# 2GHz_TDD_Driver.net
KiCad netlist of a schematic drawn in Altium Designer
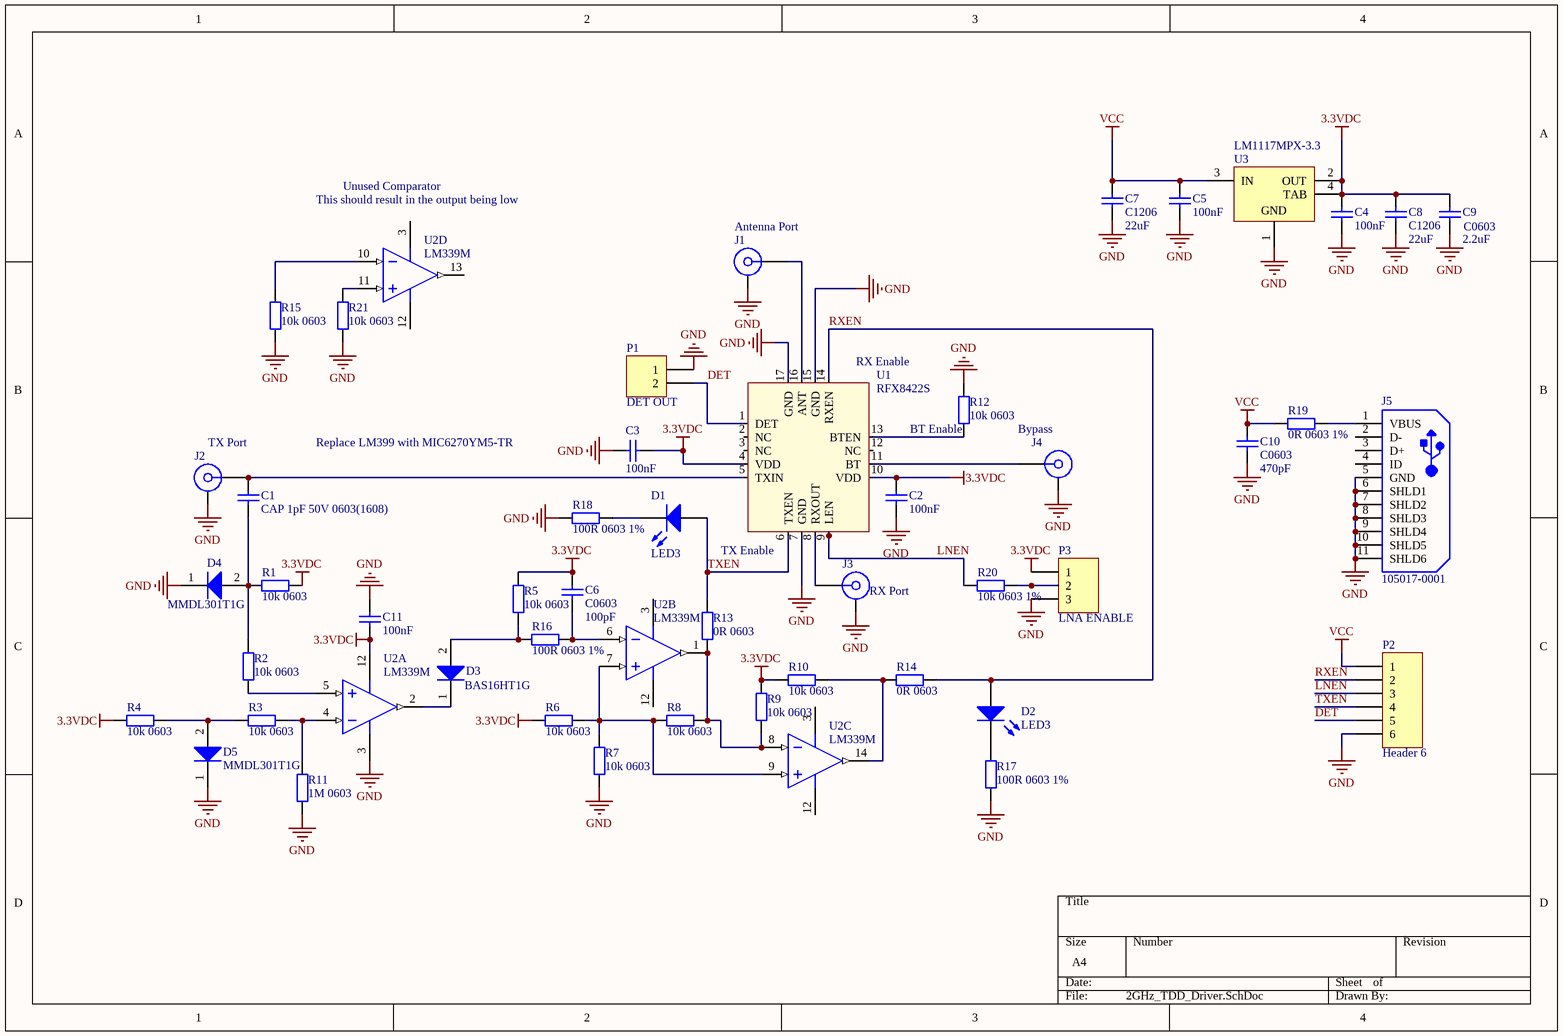
[diagram p0: 2GHz_TDD_Driver.SchDoc]

(export (version "E")
  (design (tool "Eeschema 10.0.6"))
  (components
    (comp (ref "C1")
      (value "CAP 1pF 50V 0603(1608)")
      (footprint "CAPC0603(1608)100_M")
      (description "CAP 1pF 50V ±0.25pF 0603 (1608 Metric) Thickness 1mm SMD")
      (fields (field (name "TOLERANCE") "Â±0.25pF"))
      (libsource (lib "Altium Content Vault") (part "CAP"))
    )
    (comp (ref "C2")
      (value "100nF")
      (footprint "CAPC0603(1608)100_N")
      (description "CAP 100nF 25V ±20% 0603 (1608 Metric) Thickness 1mm SMD")
      (fields (field (name "TOLERANCE") "Â±20%"))
      (libsource (lib "Altium Content Vault") (part "CMP-1035-02589-1"))
    )
    (comp (ref "C3")
      (value "100nF")
      (footprint "CAPC0603(1608)100_N")
      (description "CAP 100nF 25V ±20% 0603 (1608 Metric) Thickness 1mm SMD")
      (fields (field (name "TOLERANCE") "Â±20%"))
      (libsource (lib "Altium Content Vault") (part "CMP-1035-02589-1"))
    )
    (comp (ref "C4")
      (value "100nF")
      (footprint "CAPC0603(1608)100_N")
      (description "CAP 100nF 25V ±20% 0603 (1608 Metric) Thickness 1mm SMD")
      (fields (field (name "TOLERANCE") "Â±20%"))
      (libsource (lib "Altium Content Vault") (part "CMP-1035-02589-1"))
    )
    (comp (ref "C5")
      (value "100nF")
      (footprint "CAPC0603(1608)100_N")
      (description "CAP 100nF 25V ±20% 0603 (1608 Metric) Thickness 1mm SMD")
      (fields (field (name "TOLERANCE") "Â±20%"))
      (libsource (lib "Altium Content Vault") (part "CMP-1035-02589-1"))
    )
    (comp (ref "C6")
      (value "C0603")
      (footprint "0603")
      (description "Ceramic Chip Capacitor - Standard")
      (fields (field (name "ALTIUM_VALUE") "100pF") (field (name "PUBLISHER") "Altium Limited"))
      (libsource (lib "KEMET Chip Capacitor") (part "C0603"))
    )
    (comp (ref "C7")
      (value "C1206")
      (footprint "1206")
      (description "Ceramic Chip Capacitor - Standard")
      (fields (field (name "ALTIUM_VALUE") "22uF") (field (name "PUBLISHER") "Altium Limited"))
      (libsource (lib "KEMET Chip Capacitor") (part "C1206"))
    )
    (comp (ref "C8")
      (value "C1206")
      (footprint "1206")
      (description "Ceramic Chip Capacitor - Standard")
      (fields (field (name "ALTIUM_VALUE") "22uF") (field (name "PUBLISHER") "Altium Limited"))
      (libsource (lib "KEMET Chip Capacitor") (part "C1206"))
    )
    (comp (ref "C9")
      (value "C0603")
      (footprint "0603")
      (description "Ceramic Chip Capacitor - Standard")
      (fields (field (name "ALTIUM_VALUE") "2.2uF") (field (name "PUBLISHER") "Altium Limited"))
      (libsource (lib "KEMET Chip Capacitor") (part "C0603"))
    )
    (comp (ref "C10")
      (value "C0603")
      (footprint "0603")
      (description "Ceramic Chip Capacitor - Standard")
      (fields (field (name "ALTIUM_VALUE") "470pF") (field (name "PUBLISHER") "Altium Limited"))
      (libsource (lib "KEMET Chip Capacitor") (part "C0603"))
    )
    (comp (ref "C11")
      (value "100nF")
      (footprint "CAPC0603(1608)100_N")
      (description "CAP 100nF 25V ±20% 0603 (1608 Metric) Thickness 1mm SMD")
      (fields (field (name "TOLERANCE") "Â±20%"))
      (libsource (lib "Altium Content Vault") (part "CMP-1035-02589-1"))
    )
    (comp (ref "D1")
      (value "LED3")
      (footprint "3.5X2.8X1.9")
      (description "Typical BLUE SiC LED")
      (fields (field (name "PUBLISHER") "Altium Limited"))
      (libsource (lib "Miscellaneous Devices") (part "LED3"))
    )
    (comp (ref "D2")
      (value "LED3")
      (footprint "3.5X2.8X1.9")
      (description "Typical BLUE SiC LED")
      (fields (field (name "PUBLISHER") "Altium Limited"))
      (libsource (lib "Miscellaneous Devices") (part "LED3"))
    )
    (comp (ref "D3")
      (value "BAS16HT1G")
      (footprint "ONSC-SOD-323-2-477-02_V")
      (description "Switching Diode, 2-Pin SOD-323, Pb-Free, Tape and Reel")
      (fields (field (name "MANUFACTURER") "On Semiconductor"))
      (libsource (lib "Altium Content Vault") (part "ONSC-D-K1A2-2"))
    )
    (comp (ref "D4")
      (value "MMDL301T1G")
      (footprint "ONSC-SOD-323-2-477-02_V")
      (description "Silicon Hot-Carrier Diode, Schottky Barrier Diode, 2-Pin SOD-323, Pb-Free, Tape and Reel")
      (fields (field (name "MANUFACTURER") "On Semiconductor"))
      (libsource (lib "Altium Content Vault") (part "ONSC-D-K1A2-2"))
    )
    (comp (ref "D5")
      (value "MMDL301T1G")
      (footprint "ONSC-SOD-323-2-477-02_V")
      (description "Silicon Hot-Carrier Diode, Schottky Barrier Diode, 2-Pin SOD-323, Pb-Free, Tape and Reel")
      (fields (field (name "MANUFACTURER") "On Semiconductor"))
      (libsource (lib "Altium Content Vault") (part "ONSC-D-K1A2-2"))
    )
    (comp (ref "J1")
      (value "32K145-400L5")
      (footprint "ROS-32K145-400L5_V")
      (description "SMA Right Angle Jack, Edge Mount, Up to 18 GHz, -55 to 155 degC")
      (libsource (lib "Rosenberger SMA") (part "32K145-400L5"))
    )
    (comp (ref "J2")
      (value "32K145-400L5")
      (footprint "ROS-32K145-400L5_V")
      (description "SMA Right Angle Jack, Edge Mount, Up to 18 GHz, -55 to 155 degC")
      (libsource (lib "Rosenberger SMA") (part "32K145-400L5"))
    )
    (comp (ref "J3")
      (value "32K145-400L5")
      (footprint "ROS-32K145-400L5_V")
      (description "SMA Right Angle Jack, Edge Mount, Up to 18 GHz, -55 to 155 degC")
      (libsource (lib "Rosenberger SMA") (part "32K145-400L5"))
    )
    (comp (ref "J4")
      (value "32K145-400L5")
      (footprint "ROS-32K145-400L5_V")
      (description "SMA Right Angle Jack, Edge Mount, Up to 18 GHz, -55 to 155 degC")
      (libsource (lib "Rosenberger SMA") (part "32K145-400L5"))
    )
    (comp (ref "J5")
      (value "105017-0001")
      (footprint "USB-MICRO-B_V")
      (fields (field (name "MANUFACTURER") "Molex"))
      (libsource (lib "Altium Content Vault") (part "USB-5-6SHLD"))
    )
    (comp (ref "P1")
      (value "DET OUT")
      (footprint "HDR1X2")
      (description "Header, 2-Pin")
      (fields (field (name "PUBLISHER") "Altium Limited"))
      (libsource (lib "Miscellaneous Connectors") (part "Header 2"))
    )
    (comp (ref "P2")
      (value "Header 6")
      (footprint "HDR1X6")
      (description "Header, 6-Pin")
      (fields (field (name "PUBLISHER") "Altium Limited"))
      (libsource (lib "Miscellaneous Connectors") (part "Header 6"))
    )
    (comp (ref "P3")
      (value "LNA ENABLE")
      (footprint "HDR1X3")
      (description "Header, 3-Pin")
      (fields (field (name "PUBLISHER") "Altium Limited"))
      (libsource (lib "Miscellaneous Connectors") (part "Header 3"))
    )
    (comp (ref "R1")
      (value "10k 0603")
      (footprint "R0603")
      (description "10k 0603 1% resistor")
      (fields (field (name "PUBLISHER") "iv"))
      (libsource (lib "") (part "10k 0603_2"))
    )
    (comp (ref "R2")
      (value "10k 0603")
      (footprint "R0603")
      (description "10k 0603 1% resistor")
      (fields (field (name "PUBLISHER") "iv"))
      (libsource (lib "") (part "10k 0603_3"))
    )
    (comp (ref "R3")
      (value "10k 0603")
      (footprint "R0603")
      (description "10k 0603 1% resistor")
      (fields (field (name "PUBLISHER") "iv"))
      (libsource (lib "ftg_lib") (part "10k 0603"))
    )
    (comp (ref "R4")
      (value "10k 0603")
      (footprint "R0603")
      (description "10k 0603 1% resistor")
      (fields (field (name "PUBLISHER") "iv"))
      (libsource (lib "ftg_lib") (part "10k 0603"))
    )
    (comp (ref "R5")
      (value "10k 0603")
      (footprint "R0603")
      (description "10k 0603 1% resistor")
      (fields (field (name "PUBLISHER") "iv"))
      (libsource (lib "") (part "10k 0603_1"))
    )
    (comp (ref "R6")
      (value "10k 0603")
      (footprint "R0603")
      (description "10k 0603 1% resistor")
      (fields (field (name "PUBLISHER") "iv"))
      (libsource (lib "ftg_lib") (part "10k 0603"))
    )
    (comp (ref "R7")
      (value "10k 0603")
      (footprint "R0603")
      (description "10k 0603 1% resistor")
      (fields (field (name "PUBLISHER") "iv"))
      (libsource (lib "") (part "10k 0603_1"))
    )
    (comp (ref "R8")
      (value "10k 0603")
      (footprint "R0603")
      (description "10k 0603 1% resistor")
      (fields (field (name "PUBLISHER") "iv"))
      (libsource (lib "ftg_lib") (part "10k 0603"))
    )
    (comp (ref "R9")
      (value "10k 0603")
      (footprint "R0603")
      (description "10k 0603 1% resistor")
      (fields (field (name "PUBLISHER") "iv"))
      (libsource (lib "") (part "10k 0603_1"))
    )
    (comp (ref "R10")
      (value "10k 0603")
      (footprint "R0603")
      (description "10k 0603 1% resistor")
      (fields (field (name "PUBLISHER") "iv"))
      (libsource (lib "ftg_lib") (part "10k 0603"))
    )
    (comp (ref "R11")
      (value "1M 0603")
      (footprint "R0603")
      (description "1M 0603 1%")
      (libsource (lib "ftg_lib") (part "0R 0603"))
    )
    (comp (ref "R12")
      (value "10k 0603")
      (footprint "R0603")
      (description "10k 0603 1% resistor")
      (fields (field (name "PUBLISHER") "iv"))
      (libsource (lib "") (part "10k 0603_1"))
    )
    (comp (ref "R13")
      (value "0R 0603")
      (footprint "R0603")
      (description "0R 0603 1%")
      (libsource (lib "ftg_lib") (part "0R 0603"))
    )
    (comp (ref "R14")
      (value "0R 0603")
      (footprint "R0603")
      (description "0R 0603 1%")
      (libsource (lib "") (part "0R 0603_1"))
    )
    (comp (ref "R15")
      (value "10k 0603")
      (footprint "R0603")
      (description "10k 0603 1% resistor")
      (fields (field (name "PUBLISHER") "iv"))
      (libsource (lib "2GHz_TDD_Driver") (part "10k 0603"))
    )
    (comp (ref "R16")
      (value "100R 0603 1%")
      (footprint "R0603")
      (fields (field (name "TOLERANCE") "1%") (field (name "PUBLISHER") "iv"))
      (libsource (lib "ftg_lib") (part "100R 0603"))
    )
    (comp (ref "R17")
      (value "100R 0603 1%")
      (footprint "R0603")
      (fields (field (name "TOLERANCE") "1%") (field (name "PUBLISHER") "iv"))
      (libsource (lib "") (part "100R 0603_1"))
    )
    (comp (ref "R18")
      (value "100R 0603 1%")
      (footprint "R0603")
      (fields (field (name "TOLERANCE") "1%") (field (name "PUBLISHER") "iv"))
      (libsource (lib "") (part "100R 0603_2"))
    )
    (comp (ref "R19")
      (value "0R 0603 1%")
      (footprint "R0603")
      (fields (field (name "TOLERANCE") "1%") (field (name "PUBLISHER") "iv"))
      (libsource (lib "") (part "0R 0603_1"))
    )
    (comp (ref "R20")
      (value "10k 0603 1%")
      (footprint "R0603")
      (description "10k 0603 1% resistor")
      (fields (field (name "TOLERANCE") "1%") (field (name "PUBLISHER") "iv"))
      (libsource (lib "ftg_lib") (part "10k 0603"))
    )
    (comp (ref "R21")
      (value "10k 0603")
      (footprint "R0603")
      (description "10k 0603 1% resistor")
      (fields (field (name "PUBLISHER") "iv"))
      (libsource (lib "2GHz_TDD_Driver") (part "10k 0603"))
    )
    (comp (ref "U1")
      (value "RFX8422S")
      (footprint "QFN50P250X250X50_HS-17M")
      (description "2.4GHZ PA+LNA+SW +21dBm")
      (fields (field (name "MANUFACTURER") "Skyworks Solutions"))
      (libsource (lib "ftg_lib") (part "RFX8422S"))
    )
    (comp (ref "U2")
      (value "LM339M")
      (footprint "D0014A_N")
      (description "Low Power Low Offset Voltage Quad Comparator, 14-pin Narrow SOIC")
      (fields (field (name "MANUFACTURER") "Texas Instruments"))
      (libsource (lib "2GHz_TDD_Driver") (part "CMP-0055-00762-3"))
    )
    (comp (ref "U3")
      (value "LM1117MPX-3.3")
      (footprint "DCY0004A_N")
      (description "800mA Low-Dropout Linear Regulator, 4-pin SOT-223")
      (fields (field (name "MANUFACTURER") "Texas Instruments"))
      (libsource (lib "Altium Content Vault") (part "PM-REG-LM1086-SOT4"))
    )
  )
  (nets
    (net (code "1") (name "/DET") (class "Default")
      (node (ref "P1") (pin "2") (pinfunction "2_2") (pintype "passive"))
      (node (ref "P2") (pin "5") (pinfunction "5_5") (pintype "passive"))
      (node (ref "U1") (pin "1") (pinfunction "DET_1") (pintype "input"))
    )
    (net (code "2") (name "/LNEN") (class "Default")
      (node (ref "P2") (pin "3") (pinfunction "3_3") (pintype "passive"))
      (node (ref "R20") (pin "1") (pinfunction "1_1") (pintype "passive"))
      (node (ref "U1") (pin "9") (pinfunction "LEN_9") (pintype "input"))
    )
    (net (code "3") (name "/RXEN") (class "Default")
      (node (ref "D2") (pin "1") (pinfunction "A_1") (pintype "passive"))
      (node (ref "P2") (pin "2") (pinfunction "2_2") (pintype "passive"))
      (node (ref "R14") (pin "2") (pinfunction "2_2") (pintype "passive"))
      (node (ref "U1") (pin "14") (pinfunction "RXEN_14") (pintype "input"))
    )
    (net (code "4") (name "/TXEN") (class "Default")
      (node (ref "D1") (pin "1") (pinfunction "A_1") (pintype "passive"))
      (node (ref "P2") (pin "4") (pinfunction "4_4") (pintype "passive"))
      (node (ref "R13") (pin "2") (pinfunction "2_2") (pintype "passive"))
      (node (ref "U1") (pin "6") (pinfunction "TXEN_6") (pintype "input"))
    )
    (net (code "5") (name "3.3VDC") (class "Default")
      (node (ref "C11") (pin "2") (pinfunction "2_2") (pintype "passive"))
      (node (ref "C2") (pin "2") (pinfunction "2_2") (pintype "passive"))
      (node (ref "C3") (pin "1") (pinfunction "1_1") (pintype "passive"))
      (node (ref "C4") (pin "2") (pinfunction "2_2") (pintype "passive"))
      (node (ref "C6") (pin "2") (pinfunction "2_2") (pintype "passive"))
      (node (ref "C8") (pin "2") (pinfunction "2_2") (pintype "passive"))
      (node (ref "C9") (pin "2") (pinfunction "2_2") (pintype "passive"))
      (node (ref "P3") (pin "1") (pinfunction "1_1") (pintype "passive"))
      (node (ref "R1") (pin "1") (pinfunction "1_1") (pintype "passive"))
      (node (ref "R10") (pin "1") (pinfunction "1_1") (pintype "passive"))
      (node (ref "R4") (pin "1") (pinfunction "1_1") (pintype "passive"))
      (node (ref "R5") (pin "2") (pinfunction "2_2") (pintype "passive"))
      (node (ref "R6") (pin "1") (pinfunction "1_1") (pintype "passive"))
      (node (ref "R9") (pin "2") (pinfunction "2_2") (pintype "passive"))
      (node (ref "U1") (pin "10") (pinfunction "VDD_10") (pintype "input"))
      (node (ref "U1") (pin "4") (pinfunction "VDD_4") (pintype "input"))
      (node (ref "U2") (pin "12") (pinfunction "GND_12") (pintype "power_in"))
      (node (ref "U3") (pin "2") (pinfunction "OUT_2") (pintype "power_in"))
      (node (ref "U3") (pin "4") (pinfunction "TAB_4") (pintype "power_in"))
    )
    (net (code "6") (name "GND") (class "Default")
      (node (ref "C10") (pin "1") (pinfunction "1_1") (pintype "passive"))
      (node (ref "C11") (pin "1") (pinfunction "1_1") (pintype "passive"))
      (node (ref "C2") (pin "1") (pinfunction "1_1") (pintype "passive"))
      (node (ref "C3") (pin "2") (pinfunction "2_2") (pintype "passive"))
      (node (ref "C4") (pin "1") (pinfunction "1_1") (pintype "passive"))
      (node (ref "C5") (pin "1") (pinfunction "1_1") (pintype "passive"))
      (node (ref "C7") (pin "1") (pinfunction "1_1") (pintype "passive"))
      (node (ref "C8") (pin "1") (pinfunction "1_1") (pintype "passive"))
      (node (ref "C9") (pin "1") (pinfunction "1_1") (pintype "passive"))
      (node (ref "D4") (pin "1") (pinfunction "K_1") (pintype "passive"))
      (node (ref "D5") (pin "1") (pinfunction "K_1") (pintype "passive"))
      (node (ref "J1") (pin "MP") (pinfunction "MP_MP") (pintype "passive"))
      (node (ref "J2") (pin "MP") (pinfunction "MP_MP") (pintype "passive"))
      (node (ref "J3") (pin "MP") (pinfunction "MP_MP") (pintype "passive"))
      (node (ref "J4") (pin "MP") (pinfunction "MP_MP") (pintype "passive"))
      (node (ref "J5") (pin "10") (pinfunction "SHLD5_10") (pintype "passive"))
      (node (ref "J5") (pin "11") (pinfunction "SHLD6_11") (pintype "passive"))
      (node (ref "J5") (pin "5") (pinfunction "GND_5") (pintype "passive"))
      (node (ref "J5") (pin "6") (pinfunction "SHLD1_6") (pintype "passive"))
      (node (ref "J5") (pin "7") (pinfunction "SHLD2_7") (pintype "passive"))
      (node (ref "J5") (pin "8") (pinfunction "SHLD3_8") (pintype "passive"))
      (node (ref "J5") (pin "9") (pinfunction "SHLD4_9") (pintype "passive"))
      (node (ref "P1") (pin "1") (pinfunction "1_1") (pintype "passive"))
      (node (ref "P2") (pin "6") (pinfunction "6_6") (pintype "passive"))
      (node (ref "P3") (pin "3") (pinfunction "3_3") (pintype "passive"))
      (node (ref "R11") (pin "1") (pinfunction "1_1") (pintype "passive"))
      (node (ref "R12") (pin "2") (pinfunction "2_2") (pintype "passive"))
      (node (ref "R15") (pin "1") (pinfunction "1_1") (pintype "passive"))
      (node (ref "R17") (pin "1") (pinfunction "1_1") (pintype "passive"))
      (node (ref "R18") (pin "2") (pinfunction "2_2") (pintype "passive"))
      (node (ref "R21") (pin "1") (pinfunction "1_1") (pintype "passive"))
      (node (ref "R7") (pin "1") (pinfunction "1_1") (pintype "passive"))
      (node (ref "U1") (pin "15") (pinfunction "GND_15") (pintype "input"))
      (node (ref "U1") (pin "17") (pinfunction "GND_17") (pintype "input"))
      (node (ref "U1") (pin "7") (pinfunction "GND_7") (pintype "input"))
      (node (ref "U2") (pin "3") (pinfunction "V+_3") (pintype "power_in"))
      (node (ref "U3") (pin "1") (pinfunction "GND_1") (pintype "power_in"))
    )
    (net (code "7") (name "Net-(D1-K)") (class "Default")
      (node (ref "D1") (pin "2") (pinfunction "K_2") (pintype "passive"))
      (node (ref "R18") (pin "1") (pinfunction "1_1") (pintype "passive"))
    )
    (net (code "8") (name "Net-(D2-K)") (class "Default")
      (node (ref "D2") (pin "2") (pinfunction "K_2") (pintype "passive"))
      (node (ref "R17") (pin "2") (pinfunction "2_2") (pintype "passive"))
    )
    (net (code "9") (name "Net-(D3-A)") (class "Default")
      (node (ref "D3") (pin "2") (pinfunction "A_2") (pintype "passive"))
      (node (ref "R16") (pin "1") (pinfunction "1_1") (pintype "passive"))
      (node (ref "R5") (pin "1") (pinfunction "1_1") (pintype "passive"))
    )
    (net (code "10") (name "Net-(D3-K)") (class "Default")
      (node (ref "D3") (pin "1") (pinfunction "K_1") (pintype "passive"))
      (node (ref "U2") (pin "2") (pinfunction "OUT1_2") (pintype "output"))
    )
    (net (code "11") (name "Net-(D4-A)") (class "Default")
      (node (ref "C1") (pin "1") (pinfunction "1_1") (pintype "passive"))
      (node (ref "D4") (pin "2") (pinfunction "A_2") (pintype "passive"))
      (node (ref "R1") (pin "2") (pinfunction "2_2") (pintype "passive"))
      (node (ref "R2") (pin "1") (pinfunction "1_1") (pintype "passive"))
    )
    (net (code "12") (name "Net-(D5-A)") (class "Default")
      (node (ref "D5") (pin "2") (pinfunction "A_2") (pintype "passive"))
      (node (ref "R3") (pin "1") (pinfunction "1_1") (pintype "passive"))
      (node (ref "R4") (pin "2") (pinfunction "2_2") (pintype "passive"))
    )
    (net (code "13") (name "Net-(J5-VBUS)") (class "Default")
      (node (ref "J5") (pin "1") (pinfunction "VBUS_1") (pintype "passive"))
      (node (ref "R19") (pin "2") (pinfunction "2_2") (pintype "passive"))
    )
    (net (code "14") (name "Net-(P3-Pad2)") (class "Default")
      (node (ref "P3") (pin "2") (pinfunction "2_2") (pintype "passive"))
      (node (ref "R20") (pin "2") (pinfunction "2_2") (pintype "passive"))
    )
    (net (code "15") (name "Net-(U1-ANT)") (class "Default")
      (node (ref "J1") (pin "1") (pinfunction "1_1") (pintype "passive"))
      (node (ref "U1") (pin "16") (pinfunction "ANT_16") (pintype "input"))
    )
    (net (code "16") (name "Net-(U1-BT)") (class "Default")
      (node (ref "J4") (pin "1") (pinfunction "1_1") (pintype "passive"))
      (node (ref "U1") (pin "11") (pinfunction "BT_11") (pintype "input"))
    )
    (net (code "17") (name "Net-(U1-BTEN)") (class "Default")
      (node (ref "R12") (pin "1") (pinfunction "1_1") (pintype "passive"))
      (node (ref "U1") (pin "13") (pinfunction "BTEN_13") (pintype "input"))
    )
    (net (code "18") (name "Net-(U1-RXOUT)") (class "Default")
      (node (ref "J3") (pin "1") (pinfunction "1_1") (pintype "passive"))
      (node (ref "U1") (pin "8") (pinfunction "RXOUT_8") (pintype "input"))
    )
    (net (code "19") (name "Net-(U1-TXIN)") (class "Default")
      (node (ref "C1") (pin "2") (pinfunction "2_2") (pintype "passive"))
      (node (ref "J2") (pin "1") (pinfunction "1_1") (pintype "passive"))
      (node (ref "U1") (pin "5") (pinfunction "TXIN_5") (pintype "input"))
    )
    (net (code "20") (name "Net-(U2A-IN1+)") (class "Default")
      (node (ref "R2") (pin "2") (pinfunction "2_2") (pintype "passive"))
      (node (ref "U2") (pin "5") (pinfunction "IN1+_5") (pintype "input"))
    )
    (net (code "21") (name "Net-(U2A-IN1-)") (class "Default")
      (node (ref "R11") (pin "2") (pinfunction "2_2") (pintype "passive"))
      (node (ref "R3") (pin "2") (pinfunction "2_2") (pintype "passive"))
      (node (ref "U2") (pin "4") (pinfunction "IN1-_4") (pintype "input"))
    )
    (net (code "22") (name "Net-(U2B-IN2+)") (class "Default")
      (node (ref "R6") (pin "2") (pinfunction "2_2") (pintype "passive"))
      (node (ref "R7") (pin "2") (pinfunction "2_2") (pintype "passive"))
      (node (ref "R8") (pin "1") (pinfunction "1_1") (pintype "passive"))
      (node (ref "U2") (pin "7") (pinfunction "IN2+_7") (pintype "input"))
      (node (ref "U2") (pin "9") (pinfunction "IN3+_9") (pintype "input"))
    )
    (net (code "23") (name "Net-(U2B-IN2-)") (class "Default")
      (node (ref "C6") (pin "1") (pinfunction "1_1") (pintype "passive"))
      (node (ref "R16") (pin "2") (pinfunction "2_2") (pintype "passive"))
      (node (ref "U2") (pin "6") (pinfunction "IN2-_6") (pintype "input"))
    )
    (net (code "24") (name "Net-(U2B-OUT2)") (class "Default")
      (node (ref "R13") (pin "1") (pinfunction "1_1") (pintype "passive"))
      (node (ref "R8") (pin "2") (pinfunction "2_2") (pintype "passive"))
      (node (ref "R9") (pin "1") (pinfunction "1_1") (pintype "passive"))
      (node (ref "U2") (pin "1") (pinfunction "OUT2_1") (pintype "output"))
      (node (ref "U2") (pin "8") (pinfunction "IN3-_8") (pintype "input"))
    )
    (net (code "25") (name "Net-(U2C-OUT3)") (class "Default")
      (node (ref "R10") (pin "2") (pinfunction "2_2") (pintype "passive"))
      (node (ref "R14") (pin "1") (pinfunction "1_1") (pintype "passive"))
      (node (ref "U2") (pin "14") (pinfunction "OUT3_14") (pintype "output"))
    )
    (net (code "26") (name "Net-(U2D-IN4+)") (class "Default")
      (node (ref "R21") (pin "2") (pinfunction "2_2") (pintype "passive"))
      (node (ref "U2") (pin "11") (pinfunction "IN4+_11") (pintype "input"))
    )
    (net (code "27") (name "Net-(U2D-IN4-)") (class "Default")
      (node (ref "R15") (pin "2") (pinfunction "2_2") (pintype "passive"))
      (node (ref "U2") (pin "10") (pinfunction "IN4-_10") (pintype "input"))
    )
    (net (code "28") (name "VCC") (class "Default")
      (node (ref "C10") (pin "2") (pinfunction "2_2") (pintype "passive"))
      (node (ref "C5") (pin "2") (pinfunction "2_2") (pintype "passive"))
      (node (ref "C7") (pin "2") (pinfunction "2_2") (pintype "passive"))
      (node (ref "P2") (pin "1") (pinfunction "1_1") (pintype "passive"))
      (node (ref "R19") (pin "1") (pinfunction "1_1") (pintype "passive"))
      (node (ref "U3") (pin "3") (pinfunction "IN_3") (pintype "power_in"))
    )
    (net (code "29") (name "unconnected-(J5-D+-Pad3)") (class "Default")
      (node (ref "J5") (pin "3") (pinfunction "D+_3") (pintype "passive"))
    )
    (net (code "30") (name "unconnected-(J5-D--Pad2)") (class "Default")
      (node (ref "J5") (pin "2") (pinfunction "D-_2") (pintype "passive"))
    )
    (net (code "31") (name "unconnected-(J5-ID-Pad4)") (class "Default")
      (node (ref "J5") (pin "4") (pinfunction "ID_4") (pintype "passive"))
    )
    (net (code "32") (name "unconnected-(U1-NC-Pad2)") (class "Default")
      (node (ref "U1") (pin "2") (pinfunction "NC_2") (pintype "input"))
    )
    (net (code "33") (name "unconnected-(U1-NC-Pad3)") (class "Default")
      (node (ref "U1") (pin "3") (pinfunction "NC_3") (pintype "input"))
    )
    (net (code "34") (name "unconnected-(U1-NC-Pad12)") (class "Default")
      (node (ref "U1") (pin "12") (pinfunction "NC_12") (pintype "input"))
    )
    (net (code "35") (name "unconnected-(U2B-GND-Pad12)") (class "Default")
      (node (ref "U2") (pin "12") (pinfunction "GND_12") (pintype "power_in"))
    )
    (net (code "36") (name "unconnected-(U2B-V+-Pad3)") (class "Default")
      (node (ref "U2") (pin "3") (pinfunction "V+_3") (pintype "power_in"))
    )
    (net (code "37") (name "unconnected-(U2C-GND-Pad12)") (class "Default")
      (node (ref "U2") (pin "12") (pinfunction "GND_12") (pintype "power_in"))
    )
    (net (code "38") (name "unconnected-(U2C-V+-Pad3)") (class "Default")
      (node (ref "U2") (pin "3") (pinfunction "V+_3") (pintype "power_in"))
    )
    (net (code "39") (name "unconnected-(U2D-GND-Pad12)") (class "Default")
      (node (ref "U2") (pin "12") (pinfunction "GND_12") (pintype "power_in"))
    )
    (net (code "40") (name "unconnected-(U2D-OUT4-Pad13)") (class "Default")
      (node (ref "U2") (pin "13") (pinfunction "OUT4_13") (pintype "output"))
    )
    (net (code "41") (name "unconnected-(U2D-V+-Pad3)") (class "Default")
      (node (ref "U2") (pin "3") (pinfunction "V+_3") (pintype "power_in"))
    )
  )
)
